# Sheet6.net
KiCad netlist of a schematic drawn in Altium Designer
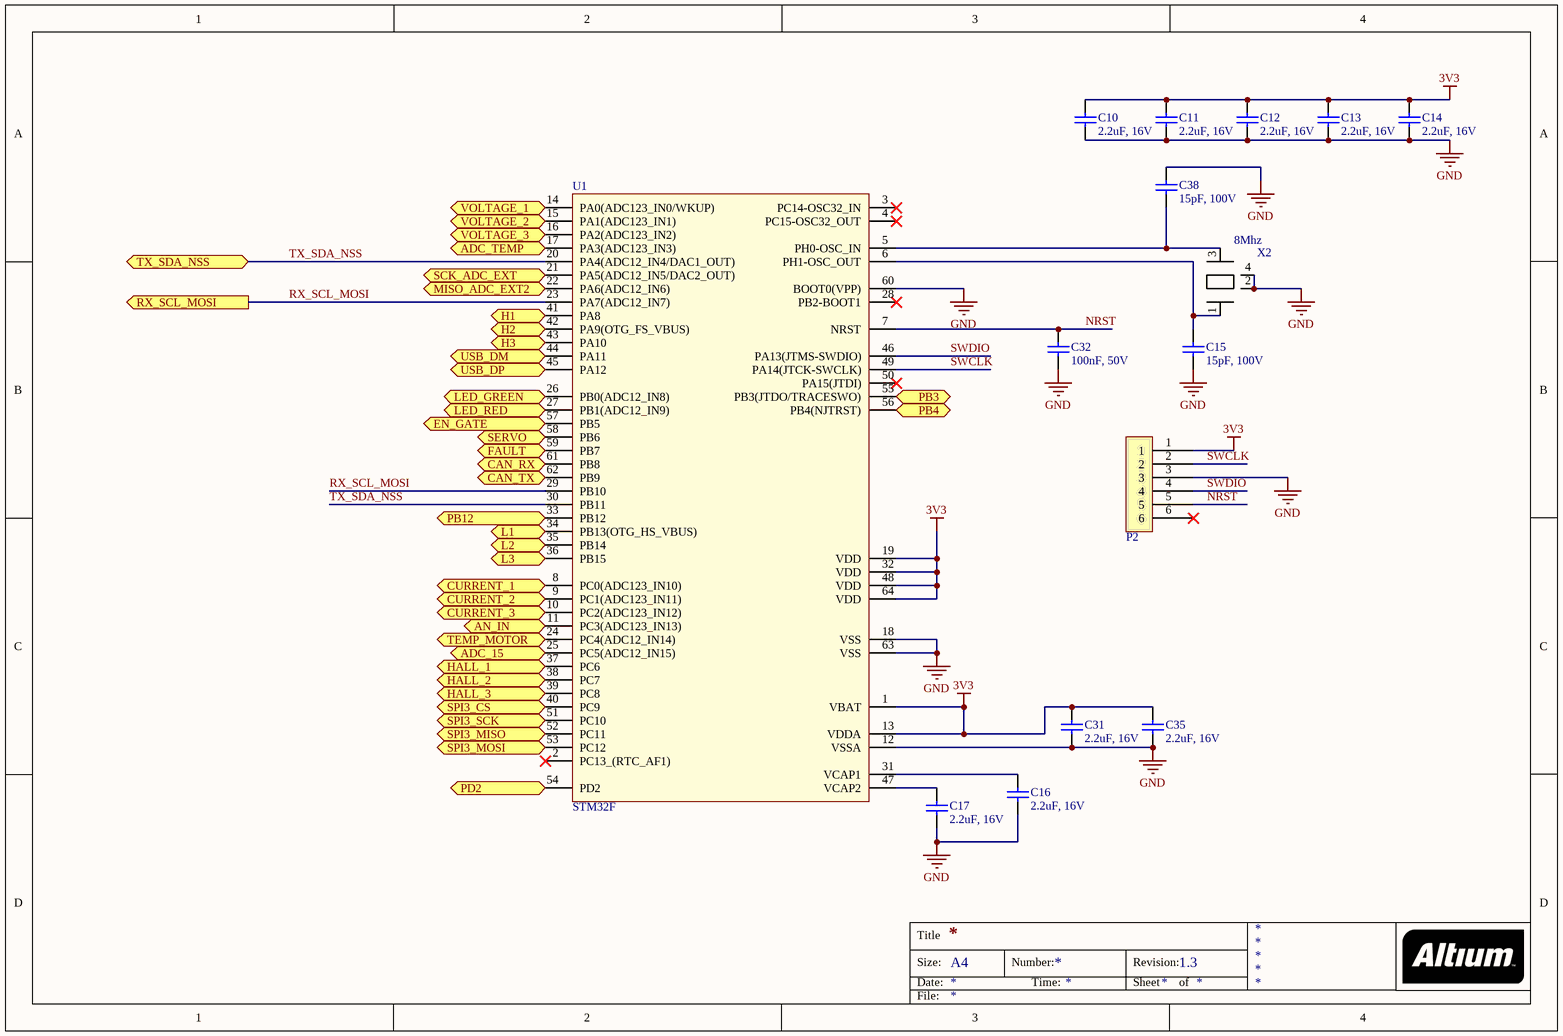
[diagram p0: Sheet6.SchDoc]

(export (version "E")
  (design (tool "Eeschema 10.0.6"))
  (components
    (comp (ref "C10")
      (value "2.2uF, 16V")
      (footprint "SMD-0603 Capacitor")
      (description "CAP 2.2u, 16V, 0603")
      (fields
        (field (name "MANUFACTURER PART NUMBER") "C1608X5R1C225M")
        (field (name "MANUFACTURER") "TDK Corporation")
      )
      (libsource (lib "Master Data Link") (part "CAP"))
    )
    (comp (ref "C11")
      (value "2.2uF, 16V")
      (footprint "SMD-0603 Capacitor")
      (description "CAP 2.2u, 16V, 0603")
      (fields
        (field (name "MANUFACTURER PART NUMBER") "C1608X5R1C225M")
        (field (name "MANUFACTURER") "TDK Corporation")
      )
      (libsource (lib "Master Data Link") (part "CAP"))
    )
    (comp (ref "C12")
      (value "2.2uF, 16V")
      (footprint "SMD-0603 Capacitor")
      (description "CAP 2.2u, 16V, 0603")
      (fields
        (field (name "MANUFACTURER PART NUMBER") "C1608X5R1C225M")
        (field (name "MANUFACTURER") "TDK Corporation")
      )
      (libsource (lib "Master Data Link") (part "CAP"))
    )
    (comp (ref "C13")
      (value "2.2uF, 16V")
      (footprint "SMD-0603 Capacitor")
      (description "CAP 2.2u, 16V, 0603")
      (fields
        (field (name "MANUFACTURER PART NUMBER") "C1608X5R1C225M")
        (field (name "MANUFACTURER") "TDK Corporation")
      )
      (libsource (lib "Master Data Link") (part "CAP"))
    )
    (comp (ref "C14")
      (value "2.2uF, 16V")
      (footprint "SMD-0603 Capacitor")
      (description "CAP 2.2u, 16V, 0603")
      (fields
        (field (name "MANUFACTURER PART NUMBER") "C1608X5R1C225M")
        (field (name "MANUFACTURER") "TDK Corporation")
      )
      (libsource (lib "Master Data Link") (part "CAP"))
    )
    (comp (ref "C15")
      (value "15pF, 100V")
      (footprint "SMD-0603 Capacitor")
      (description "CAP 15p, 100V, 0603")
      (fields
        (field (name "MANUFACTURER PART NUMBER") "GRM1885C2A150JA01")
        (field (name "MANUFACTURER") "Murata Electronics North America")
      )
      (libsource (lib "Master Data Link") (part "CAP"))
    )
    (comp (ref "C16")
      (value "2.2uF, 16V")
      (footprint "SMD-0603 Capacitor")
      (description "CAP 2.2u, 16V, 0603")
      (fields
        (field (name "MANUFACTURER PART NUMBER") "C1608X5R1C225M")
        (field (name "MANUFACTURER") "TDK Corporation")
      )
      (libsource (lib "Master Data Link") (part "CAP"))
    )
    (comp (ref "C17")
      (value "2.2uF, 16V")
      (footprint "SMD-0603 Capacitor")
      (description "CAP 2.2u, 16V, 0603")
      (fields
        (field (name "MANUFACTURER PART NUMBER") "C1608X5R1C225M")
        (field (name "MANUFACTURER") "TDK Corporation")
      )
      (libsource (lib "Master Data Link") (part "CAP"))
    )
    (comp (ref "C31")
      (value "2.2uF, 16V")
      (footprint "SMD-0603 Capacitor")
      (description "CAP 2.2u, 16V, 0603")
      (fields
        (field (name "MANUFACTURER PART NUMBER") "C1608X5R1C225M")
        (field (name "MANUFACTURER") "TDK Corporation")
      )
      (libsource (lib "Master Data Link") (part "CAP"))
    )
    (comp (ref "C32")
      (value "100nF, 50V")
      (footprint "SMD-0603 Capacitor")
      (description "CAP 100n, 50V, 0603")
      (fields
        (field (name "MANUFACTURER PART NUMBER") "06035C104JAT2A")
        (field (name "MANUFACTURER") "AVX Corporation")
      )
      (libsource (lib "Master Data Link") (part "CAP"))
    )
    (comp (ref "C35")
      (value "2.2uF, 16V")
      (footprint "SMD-0603 Capacitor")
      (description "CAP 2.2u, 16V, 0603")
      (fields
        (field (name "MANUFACTURER PART NUMBER") "C1608X5R1C225M")
        (field (name "MANUFACTURER") "TDK Corporation")
      )
      (libsource (lib "Master Data Link") (part "CAP"))
    )
    (comp (ref "C38")
      (value "15pF, 100V")
      (footprint "SMD-0603 Capacitor")
      (description "CAP 15p, 100V, 0603")
      (fields
        (field (name "MANUFACTURER PART NUMBER") "GRM1885C2A150JA01")
        (field (name "MANUFACTURER") "Murata Electronics North America")
      )
      (libsource (lib "Master Data Link") (part "CAP"))
    )
    (comp (ref "P2")
      (value "B6B-PH-K-S(LF)(SN)")
      (footprint "JST PH TH VERT 6")
      (description "JST PH Through hole Vertical 6 Pin")
      (fields (field (name "MANUFACTURER") "JST"))
      (libsource (lib "Master Data Link") (part "CON6"))
    )
    (comp (ref "U1")
      (value "STM32F")
      (footprint "TSQFP50P1200X1200X160-64")
      (description "IC MCU 32BIT 1MB FLASH 64LQFP")
      (fields
        (field (name "MANUFACTURER PART NUMBER") "STM32F405RGT6")
        (field (name "MANUFACTURER") "STMicroelectronics")
      )
      (libsource (lib "Master Data Link") (part "STM32F"))
    )
    (comp (ref "X2")
      (value "8Mhz")
      (footprint "4-SMD CRYSTAL 5X3.2mm")
      (description "Crystal 8MHz, 10PPM")
      (fields
        (field (name "MANUFACTURER PART NUMBER") "ABM3B-8.0-10-1UT")
        (field (name "MANUFACTURER") "Abracon LLC")
      )
      (libsource (lib "Master Data Link") (part "OSC_1"))
    )
  )
  (nets
    (net (code "1") (name "/ADC_15") (class "Default")
      (node (ref "U1") (pin "25") (pinfunction "PC5(ADC12_IN15)_25") (pintype "passive"))
    )
    (net (code "2") (name "/ADC_TEMP") (class "Default")
      (node (ref "U1") (pin "17") (pinfunction "PA3(ADC123_IN3)_17") (pintype "passive"))
    )
    (net (code "3") (name "/AN_IN") (class "Default")
      (node (ref "U1") (pin "11") (pinfunction "PC3(ADC123_IN13)_11") (pintype "passive"))
    )
    (net (code "4") (name "/CAN_RX") (class "Default")
      (node (ref "U1") (pin "61") (pinfunction "PB8_61") (pintype "passive"))
    )
    (net (code "5") (name "/CAN_TX") (class "Default")
      (node (ref "U1") (pin "62") (pinfunction "PB9_62") (pintype "passive"))
    )
    (net (code "6") (name "/CURRENT_1") (class "Default")
      (node (ref "U1") (pin "8") (pinfunction "PC0(ADC123_IN10)_8") (pintype "passive"))
    )
    (net (code "7") (name "/CURRENT_2") (class "Default")
      (node (ref "U1") (pin "9") (pinfunction "PC1(ADC123_IN11)_9") (pintype "passive"))
    )
    (net (code "8") (name "/CURRENT_3") (class "Default")
      (node (ref "U1") (pin "10") (pinfunction "PC2(ADC123_IN12)_10") (pintype "passive"))
    )
    (net (code "9") (name "/EN_GATE") (class "Default")
      (node (ref "U1") (pin "57") (pinfunction "PB5_57") (pintype "passive"))
    )
    (net (code "10") (name "/FAULT") (class "Default")
      (node (ref "U1") (pin "59") (pinfunction "PB7_59") (pintype "passive"))
    )
    (net (code "11") (name "/H1") (class "Default")
      (node (ref "U1") (pin "41") (pinfunction "PA8_41") (pintype "passive"))
    )
    (net (code "12") (name "/H2") (class "Default")
      (node (ref "U1") (pin "42") (pinfunction "PA9(OTG_FS_VBUS)_42") (pintype "passive"))
    )
    (net (code "13") (name "/H3") (class "Default")
      (node (ref "U1") (pin "43") (pinfunction "PA10_43") (pintype "passive"))
    )
    (net (code "14") (name "/HALL_1") (class "Default")
      (node (ref "U1") (pin "37") (pinfunction "PC6_37") (pintype "passive"))
    )
    (net (code "15") (name "/HALL_2") (class "Default")
      (node (ref "U1") (pin "38") (pinfunction "PC7_38") (pintype "passive"))
    )
    (net (code "16") (name "/HALL_3") (class "Default")
      (node (ref "U1") (pin "39") (pinfunction "PC8_39") (pintype "passive"))
    )
    (net (code "17") (name "/L1") (class "Default")
      (node (ref "U1") (pin "34") (pinfunction "PB13(OTG_HS_VBUS)_34") (pintype "passive"))
    )
    (net (code "18") (name "/L2") (class "Default")
      (node (ref "U1") (pin "35") (pinfunction "PB14_35") (pintype "passive"))
    )
    (net (code "19") (name "/L3") (class "Default")
      (node (ref "U1") (pin "36") (pinfunction "PB15_36") (pintype "passive"))
    )
    (net (code "20") (name "/LED_GREEN") (class "Default")
      (node (ref "U1") (pin "26") (pinfunction "PB0(ADC12_IN8)_26") (pintype "passive"))
    )
    (net (code "21") (name "/LED_RED") (class "Default")
      (node (ref "U1") (pin "27") (pinfunction "PB1(ADC12_IN9)_27") (pintype "passive"))
    )
    (net (code "22") (name "/MISO_ADC_EXT2") (class "Default")
      (node (ref "U1") (pin "22") (pinfunction "PA6(ADC12_IN6)_22") (pintype "passive"))
    )
    (net (code "23") (name "/NRST") (class "Default")
      (node (ref "C32") (pin "2") (pinfunction "2_2") (pintype "passive"))
      (node (ref "P2") (pin "5") (pinfunction "5_5") (pintype "passive"))
      (node (ref "U1") (pin "7") (pinfunction "NRST_7") (pintype "passive"))
    )
    (net (code "24") (name "/PB3") (class "Default")
      (node (ref "U1") (pin "55") (pinfunction "PB3(JTDO/TRACESWO)_55") (pintype "passive"))
    )
    (net (code "25") (name "/PB4") (class "Default")
      (node (ref "U1") (pin "56") (pinfunction "PB4(NJTRST)_56") (pintype "passive"))
    )
    (net (code "26") (name "/PB12") (class "Default")
      (node (ref "U1") (pin "33") (pinfunction "PB12_33") (pintype "passive"))
    )
    (net (code "27") (name "/PD2") (class "Default")
      (node (ref "U1") (pin "54") (pinfunction "PD2_54") (pintype "passive"))
    )
    (net (code "28") (name "/RX_SCL_MOSI") (class "Default")
      (node (ref "U1") (pin "23") (pinfunction "PA7(ADC12_IN7)_23") (pintype "passive"))
      (node (ref "U1") (pin "29") (pinfunction "PB10_29") (pintype "passive"))
    )
    (net (code "29") (name "/SCK_ADC_EXT") (class "Default")
      (node (ref "U1") (pin "21") (pinfunction "PA5(ADC12_IN5/DAC2_OUT)_21") (pintype "passive"))
    )
    (net (code "30") (name "/SERVO") (class "Default")
      (node (ref "U1") (pin "58") (pinfunction "PB6_58") (pintype "passive"))
    )
    (net (code "31") (name "/SPI3_CS") (class "Default")
      (node (ref "U1") (pin "40") (pinfunction "PC9_40") (pintype "passive"))
    )
    (net (code "32") (name "/SPI3_MISO") (class "Default")
      (node (ref "U1") (pin "52") (pinfunction "PC11_52") (pintype "passive"))
    )
    (net (code "33") (name "/SPI3_MOSI") (class "Default")
      (node (ref "U1") (pin "53") (pinfunction "PC12_53") (pintype "passive"))
    )
    (net (code "34") (name "/SPI3_SCK") (class "Default")
      (node (ref "U1") (pin "51") (pinfunction "PC10_51") (pintype "passive"))
    )
    (net (code "35") (name "/SWCLK") (class "Default")
      (node (ref "P2") (pin "2") (pinfunction "2_2") (pintype "passive"))
      (node (ref "U1") (pin "49") (pinfunction "PA14(JTCK-SWCLK)_49") (pintype "passive"))
    )
    (net (code "36") (name "/SWDIO") (class "Default")
      (node (ref "P2") (pin "4") (pinfunction "4_4") (pintype "passive"))
      (node (ref "U1") (pin "46") (pinfunction "PA13(JTMS-SWDIO)_46") (pintype "passive"))
    )
    (net (code "37") (name "/TEMP_MOTOR") (class "Default")
      (node (ref "U1") (pin "24") (pinfunction "PC4(ADC12_IN14)_24") (pintype "passive"))
    )
    (net (code "38") (name "/TX_SDA_NSS") (class "Default")
      (node (ref "U1") (pin "20") (pinfunction "PA4(ADC12_IN4/DAC1_OUT)_20") (pintype "passive"))
      (node (ref "U1") (pin "30") (pinfunction "PB11_30") (pintype "passive"))
    )
    (net (code "39") (name "/USB_DM") (class "Default")
      (node (ref "U1") (pin "44") (pinfunction "PA11_44") (pintype "passive"))
    )
    (net (code "40") (name "/USB_DP") (class "Default")
      (node (ref "U1") (pin "45") (pinfunction "PA12_45") (pintype "passive"))
    )
    (net (code "41") (name "/VOLTAGE_1") (class "Default")
      (node (ref "U1") (pin "14") (pinfunction "PA0(ADC123_IN0/WKUP)_14") (pintype "passive"))
    )
    (net (code "42") (name "/VOLTAGE_2") (class "Default")
      (node (ref "U1") (pin "15") (pinfunction "PA1(ADC123_IN1)_15") (pintype "passive"))
    )
    (net (code "43") (name "/VOLTAGE_3") (class "Default")
      (node (ref "U1") (pin "16") (pinfunction "PA2(ADC123_IN2)_16") (pintype "passive"))
    )
    (net (code "44") (name "3V3") (class "Default")
      (node (ref "C10") (pin "2") (pinfunction "2_2") (pintype "passive"))
      (node (ref "C11") (pin "2") (pinfunction "2_2") (pintype "passive"))
      (node (ref "C12") (pin "2") (pinfunction "2_2") (pintype "passive"))
      (node (ref "C13") (pin "2") (pinfunction "2_2") (pintype "passive"))
      (node (ref "C14") (pin "2") (pinfunction "2_2") (pintype "passive"))
      (node (ref "C31") (pin "2") (pinfunction "2_2") (pintype "passive"))
      (node (ref "C35") (pin "2") (pinfunction "2_2") (pintype "passive"))
      (node (ref "P2") (pin "1") (pinfunction "1_1") (pintype "passive"))
      (node (ref "U1") (pin "1") (pinfunction "VBAT_1") (pintype "passive"))
      (node (ref "U1") (pin "13") (pinfunction "VDDA_13") (pintype "passive"))
      (node (ref "U1") (pin "19") (pinfunction "VDD_19") (pintype "passive"))
      (node (ref "U1") (pin "32") (pinfunction "VDD_32") (pintype "passive"))
      (node (ref "U1") (pin "48") (pinfunction "VDD_48") (pintype "passive"))
      (node (ref "U1") (pin "64") (pinfunction "VDD_64") (pintype "passive"))
    )
    (net (code "45") (name "GND") (class "Default")
      (node (ref "C10") (pin "1") (pinfunction "1_1") (pintype "passive"))
      (node (ref "C11") (pin "1") (pinfunction "1_1") (pintype "passive"))
      (node (ref "C12") (pin "1") (pinfunction "1_1") (pintype "passive"))
      (node (ref "C13") (pin "1") (pinfunction "1_1") (pintype "passive"))
      (node (ref "C14") (pin "1") (pinfunction "1_1") (pintype "passive"))
      (node (ref "C15") (pin "1") (pinfunction "1_1") (pintype "passive"))
      (node (ref "C16") (pin "1") (pinfunction "1_1") (pintype "passive"))
      (node (ref "C17") (pin "1") (pinfunction "1_1") (pintype "passive"))
      (node (ref "C31") (pin "1") (pinfunction "1_1") (pintype "passive"))
      (node (ref "C32") (pin "1") (pinfunction "1_1") (pintype "passive"))
      (node (ref "C35") (pin "1") (pinfunction "1_1") (pintype "passive"))
      (node (ref "C38") (pin "2") (pinfunction "2_2") (pintype "passive"))
      (node (ref "P2") (pin "3") (pinfunction "3_3") (pintype "passive"))
      (node (ref "U1") (pin "12") (pinfunction "VSSA_12") (pintype "passive"))
      (node (ref "U1") (pin "18") (pinfunction "VSS_18") (pintype "passive"))
      (node (ref "U1") (pin "60") (pinfunction "BOOT0(VPP)_60") (pintype "passive"))
      (node (ref "U1") (pin "63") (pinfunction "VSS_63") (pintype "passive"))
      (node (ref "X2") (pin "2") (pinfunction "3_2") (pintype "passive"))
      (node (ref "X2") (pin "4") (pinfunction "4_4") (pintype "passive"))
    )
    (net (code "46") (name "Net-(U1-PH0-OSC_IN)") (class "Default")
      (node (ref "C38") (pin "1") (pinfunction "1_1") (pintype "passive"))
      (node (ref "U1") (pin "5") (pinfunction "PH0-OSC_IN_5") (pintype "passive"))
      (node (ref "X2") (pin "3") (pinfunction "2_3") (pintype "passive"))
    )
    (net (code "47") (name "Net-(U1-PH1-OSC_OUT)") (class "Default")
      (node (ref "C15") (pin "2") (pinfunction "2_2") (pintype "passive"))
      (node (ref "U1") (pin "6") (pinfunction "PH1-OSC_OUT_6") (pintype "passive"))
      (node (ref "X2") (pin "1") (pinfunction "1_1") (pintype "passive"))
    )
    (net (code "48") (name "Net-(U1-VCAP1)") (class "Default")
      (node (ref "C16") (pin "2") (pinfunction "2_2") (pintype "passive"))
      (node (ref "U1") (pin "31") (pinfunction "VCAP1_31") (pintype "passive"))
    )
    (net (code "49") (name "Net-(U1-VCAP2)") (class "Default")
      (node (ref "C17") (pin "2") (pinfunction "2_2") (pintype "passive"))
      (node (ref "U1") (pin "47") (pinfunction "VCAP2_47") (pintype "passive"))
    )
    (net (code "50") (name "unconnected-(P2-Pad6)") (class "Default")
      (node (ref "P2") (pin "6") (pinfunction "6_6") (pintype "passive+no_connect"))
    )
    (net (code "51") (name "unconnected-(U1-PA15(JTDI)-Pad50)") (class "Default")
      (node (ref "U1") (pin "50") (pinfunction "PA15(JTDI)_50") (pintype "passive+no_connect"))
    )
    (net (code "52") (name "unconnected-(U1-PB2-BOOT1-Pad28)") (class "Default")
      (node (ref "U1") (pin "28") (pinfunction "PB2-BOOT1_28") (pintype "passive+no_connect"))
    )
    (net (code "53") (name "unconnected-(U1-PC13_(RTC_AF1)-Pad2)") (class "Default")
      (node (ref "U1") (pin "2") (pinfunction "PC13_(RTC_AF1)_2") (pintype "passive+no_connect"))
    )
    (net (code "54") (name "unconnected-(U1-PC14-OSC32_IN-Pad3)") (class "Default")
      (node (ref "U1") (pin "3") (pinfunction "PC14-OSC32_IN_3") (pintype "passive+no_connect"))
    )
    (net (code "55") (name "unconnected-(U1-PC15-OSC32_OUT-Pad4)") (class "Default")
      (node (ref "U1") (pin "4") (pinfunction "PC15-OSC32_OUT_4") (pintype "passive+no_connect"))
    )
  )
)
